# PCBMINI2.net
KiCad netlist of a schematic drawn in EAGLE
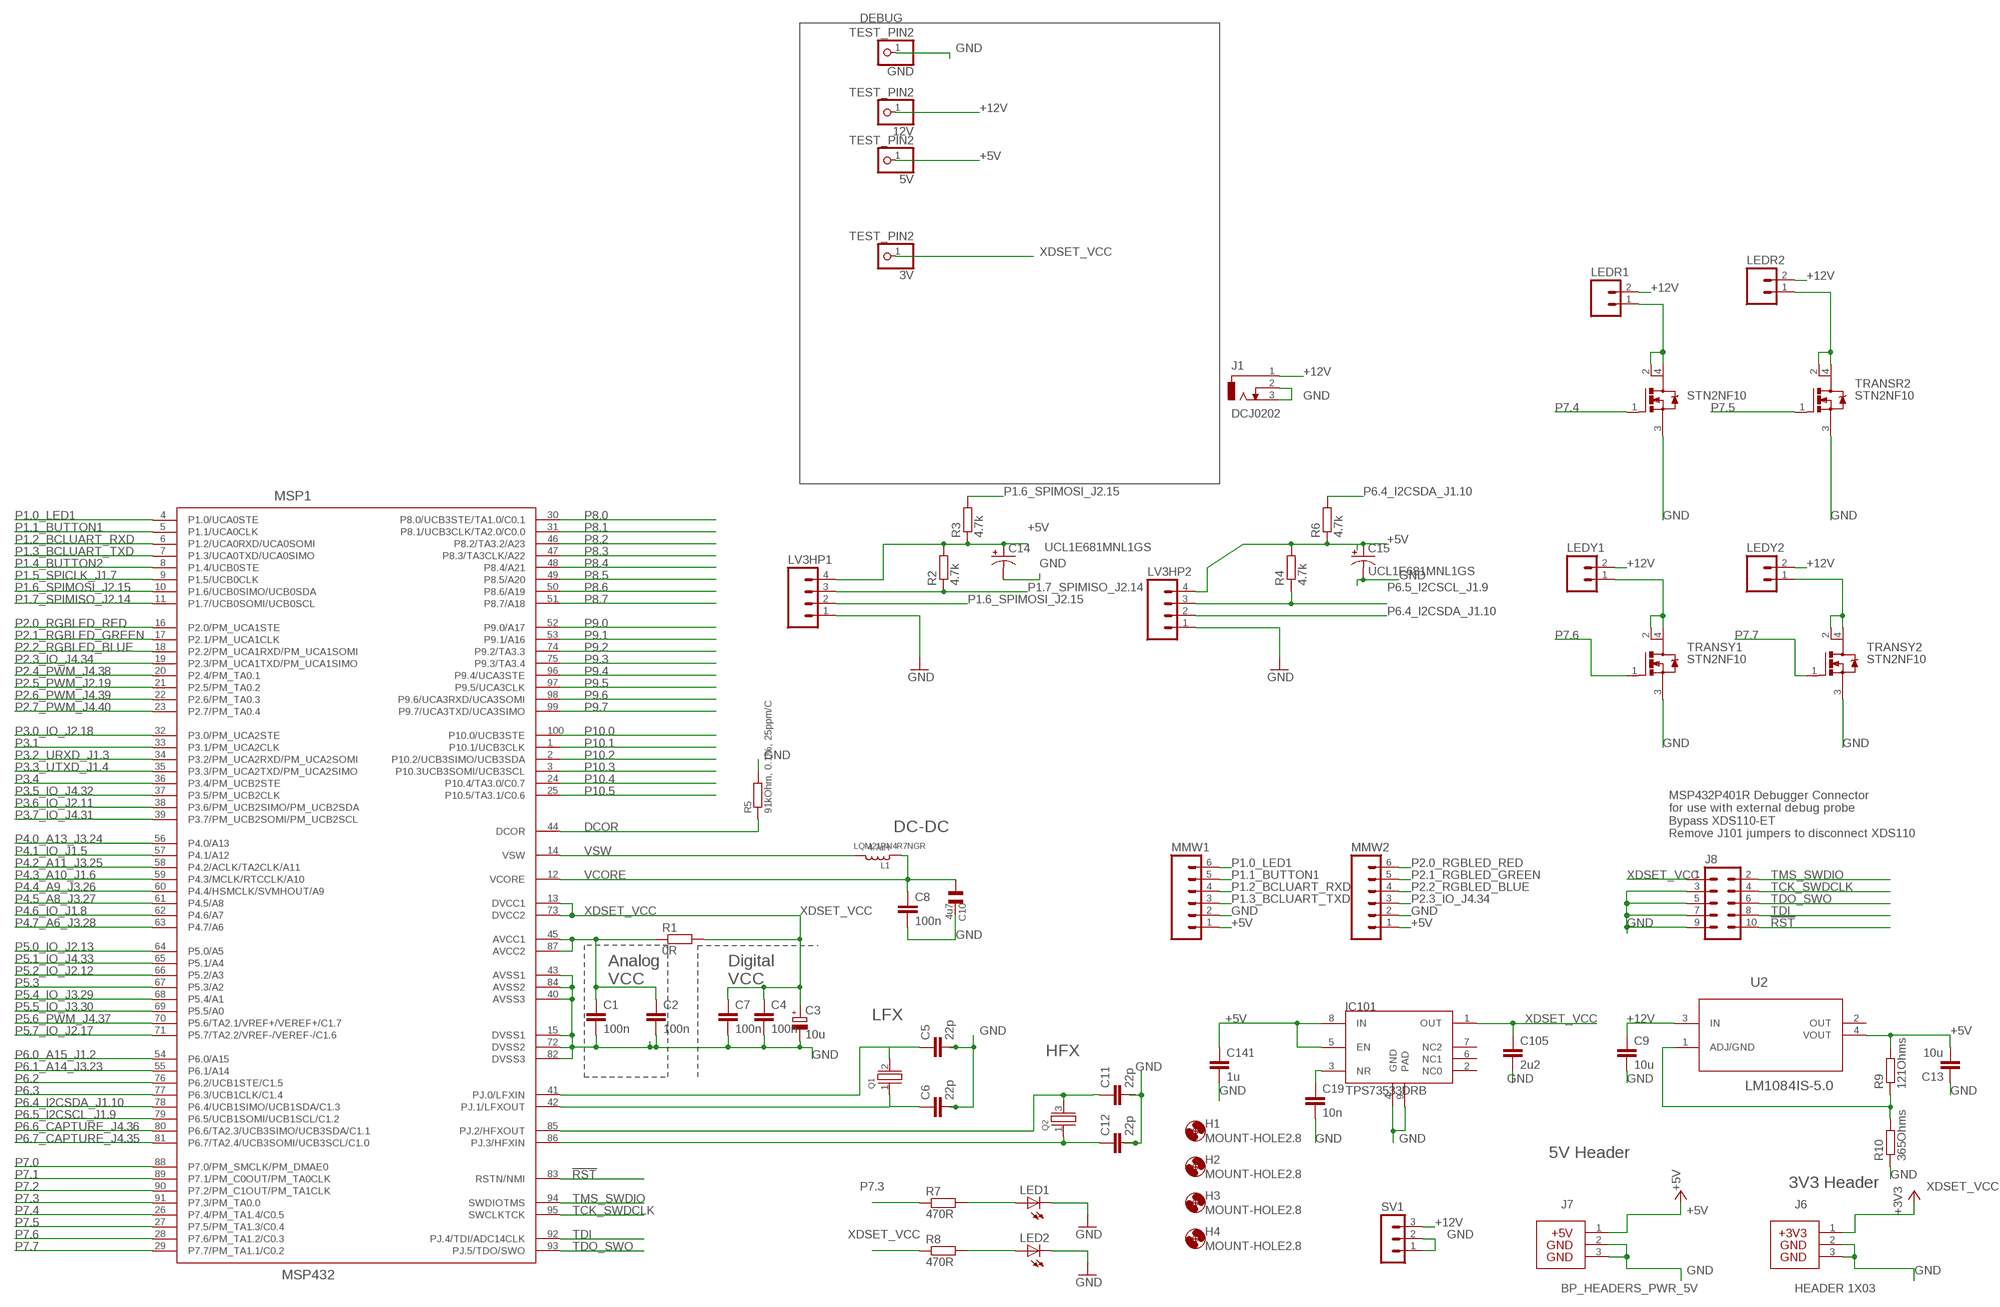
[diagram p0: schematic, sheet 1, part 1 of 2]
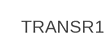
[diagram p1: schematic, sheet 1, part 2 of 2]

(export (version "E")
  (design (tool "Eeschema 10.0.6"))
  (components
    (comp (ref "3V")
      (value "TEST_PIN2")
      (footprint "eagle-import:1X01")
      (libsource (lib "eagle-import") (part "PINHD-1X1"))
    )
    (comp (ref "5V")
      (value "TEST_PIN2")
      (footprint "eagle-import:1X01")
      (libsource (lib "eagle-import") (part "PINHD-1X1"))
    )
    (comp (ref "12V")
      (value "TEST_PIN2")
      (footprint "eagle-import:1X01")
      (libsource (lib "eagle-import") (part "PINHD-1X1"))
    )
    (comp (ref "C1")
      (value "100n")
      (footprint "eagle-import:C0805")
      (libsource (lib "eagle-import") (part "C"))
    )
    (comp (ref "C2")
      (value "100n")
      (footprint "eagle-import:C0805")
      (libsource (lib "eagle-import") (part "C"))
    )
    (comp (ref "C3")
      (value "10u")
      (footprint "eagle-import:A_3216-18R")
      (libsource (lib "eagle-import") (part "CPOL-EUA/3216-18R"))
    )
    (comp (ref "C4")
      (value "100n")
      (footprint "eagle-import:C0805")
      (libsource (lib "eagle-import") (part "C"))
    )
    (comp (ref "C5")
      (value "22p")
      (footprint "eagle-import:C0805")
      (libsource (lib "eagle-import") (part "C"))
    )
    (comp (ref "C6")
      (value "22p")
      (footprint "eagle-import:C0805")
      (libsource (lib "eagle-import") (part "C"))
    )
    (comp (ref "C7")
      (value "100n")
      (footprint "eagle-import:C0805")
      (libsource (lib "eagle-import") (part "C"))
    )
    (comp (ref "C8")
      (value "100n")
      (footprint "eagle-import:C0805")
      (libsource (lib "eagle-import") (part "C"))
    )
    (comp (ref "C9")
      (value "10u")
      (footprint "eagle-import:C0805")
      (libsource (lib "eagle-import") (part "C"))
    )
    (comp (ref "C10")
      (value "4u7")
      (footprint "eagle-import:CSMD0805")
      (libsource (lib "eagle-import") (part "CSMD0805"))
    )
    (comp (ref "C11")
      (value "22p")
      (footprint "eagle-import:C0805")
      (libsource (lib "eagle-import") (part "C"))
    )
    (comp (ref "C12")
      (value "22p")
      (footprint "eagle-import:C0805")
      (libsource (lib "eagle-import") (part "C"))
    )
    (comp (ref "C13")
      (value "10u")
      (footprint "eagle-import:C0805")
      (libsource (lib "eagle-import") (part "C"))
    )
    (comp (ref "C14")
      (value "UCL1E681MNL1GS")
      (footprint "eagle-import:CAPAE1030X1350N")
      (fields (field (name "MF") "Nichicon"))
      (libsource (lib "eagle-import") (part "UCL1E681MNL1GS"))
    )
    (comp (ref "C15")
      (value "UCL1E681MNL1GS")
      (footprint "eagle-import:CAPAE1030X1350N")
      (fields (field (name "MF") "Nichicon"))
      (libsource (lib "eagle-import") (part "UCL1E681MNL1GS"))
    )
    (comp (ref "C19")
      (value "10n")
      (footprint "eagle-import:C0603")
      (libsource (lib "eagle-import") (part "C-EUC0603"))
    )
    (comp (ref "C105")
      (value "2u2")
      (footprint "eagle-import:C0603")
      (libsource (lib "eagle-import") (part "C-EUC0603"))
    )
    (comp (ref "C141")
      (value "1u")
      (footprint "eagle-import:C0603")
      (libsource (lib "eagle-import") (part "C-EUC0603"))
    )
    (comp (ref "GND")
      (value "TEST_PIN2")
      (footprint "eagle-import:1X01")
      (libsource (lib "eagle-import") (part "PINHD-1X1"))
    )
    (comp (ref "H1")
      (value "MOUNT-HOLE2.8")
      (footprint "eagle-import:2,8")
      (libsource (lib "eagle-import") (part "MOUNT-HOLE2.8"))
    )
    (comp (ref "H2")
      (value "MOUNT-HOLE2.8")
      (footprint "eagle-import:2,8")
      (libsource (lib "eagle-import") (part "MOUNT-HOLE2.8"))
    )
    (comp (ref "H3")
      (value "MOUNT-HOLE2.8")
      (footprint "eagle-import:2,8")
      (libsource (lib "eagle-import") (part "MOUNT-HOLE2.8"))
    )
    (comp (ref "H4")
      (value "MOUNT-HOLE2.8")
      (footprint "eagle-import:2,8")
      (libsource (lib "eagle-import") (part "MOUNT-HOLE2.8"))
    )
    (comp (ref "IC101")
      (value "TPS73533DRB")
      (footprint "eagle-import:SON8")
      (libsource (lib "eagle-import") (part "TPS73633DRB"))
    )
    (comp (ref "J1")
      (value "DCJ0202")
      (footprint "eagle-import:DCJ0202")
      (libsource (lib "eagle-import") (part "DCJ0202"))
    )
    (comp (ref "J6")
      (value "HEADER 1X03")
      (footprint "eagle-import:3PIN_PWR_3V3")
      (libsource (lib "eagle-import") (part "BP_HEADERS_PWR_3V3-TH100"))
    )
    (comp (ref "J7")
      (value "BP_HEADERS_PWR_5V")
      (footprint "eagle-import:3PIN_PWR_5V")
      (libsource (lib "eagle-import") (part "BP_HEADERS_PWR_5V"))
    )
    (comp (ref "J8")
      (value "DEBUG_ARM-10")
      (footprint "eagle-import:ARM-10")
      (libsource (lib "eagle-import") (part "DEBUG_ARM-10"))
    )
    (comp (ref "L1")
      (value "4.7uH")
      (footprint "eagle-import:0806")
      (libsource (lib "eagle-import") (part "LQM2MP_G0"))
    )
    (comp (ref "LED1")
      (value "LED_E")
      (footprint "eagle-import:LED_1206")
      (libsource (lib "eagle-import") (part "LED_E"))
    )
    (comp (ref "LED2")
      (value "LED_E")
      (footprint "eagle-import:LED_1206")
      (libsource (lib "eagle-import") (part "LED_E"))
    )
    (comp (ref "LEDR1")
      (value "MA02")
      (footprint "eagle-import:02PA")
      (libsource (lib "eagle-import") (part "MA02"))
    )
    (comp (ref "LEDR2")
      (value "MA02")
      (footprint "eagle-import:02PA")
      (libsource (lib "eagle-import") (part "MA02"))
    )
    (comp (ref "LEDY1")
      (value "MA02")
      (footprint "eagle-import:02PA")
      (libsource (lib "eagle-import") (part "MA02"))
    )
    (comp (ref "LEDY2")
      (value "MA02")
      (footprint "eagle-import:02PA")
      (libsource (lib "eagle-import") (part "MA02"))
    )
    (comp (ref "LV3HP1")
      (value "MA04")
      (footprint "eagle-import:04PA")
      (libsource (lib "eagle-import") (part "MA04"))
    )
    (comp (ref "LV3HP2")
      (value "MA04")
      (footprint "eagle-import:04PA")
      (libsource (lib "eagle-import") (part "MA04"))
    )
    (comp (ref "MMW1")
      (value "MA06")
      (footprint "eagle-import:06PA")
      (libsource (lib "eagle-import") (part "MA06"))
    )
    (comp (ref "MMW2")
      (value "MA06")
      (footprint "eagle-import:06PA")
      (libsource (lib "eagle-import") (part "MA06"))
    )
    (comp (ref "MSP1")
      (value "MSP432")
      (footprint "eagle-import:PZ100")
      (libsource (lib "eagle-import") (part "MSP432"))
    )
    (comp (ref "Q1")
      (value "CRYSTALLF_GENERAL")
      (footprint "eagle-import:LF_XTAL")
      (libsource (lib "eagle-import") (part "CRYSTALLF_GENERAL"))
    )
    (comp (ref "Q2")
      (value "CRYSTALEPSON_FA-238")
      (footprint "eagle-import:FA-238")
      (libsource (lib "eagle-import") (part "CRYSTALEPSON_FA-238"))
    )
    (comp (ref "R1")
      (value "0R")
      (footprint "eagle-import:R0805")
      (libsource (lib "eagle-import") (part "R"))
    )
    (comp (ref "R2")
      (value "4.7k")
      (footprint "eagle-import:R0805")
      (libsource (lib "eagle-import") (part "R"))
    )
    (comp (ref "R3")
      (value "4.7k")
      (footprint "eagle-import:R0805")
      (libsource (lib "eagle-import") (part "R"))
    )
    (comp (ref "R4")
      (value "4.7k")
      (footprint "eagle-import:R0805")
      (libsource (lib "eagle-import") (part "R"))
    )
    (comp (ref "R5")
      (value "91kOhm, 0.1%, 25ppm/C")
      (footprint "eagle-import:0805")
      (libsource (lib "eagle-import") (part "R_0805"))
    )
    (comp (ref "R6")
      (value "4.7k")
      (footprint "eagle-import:R0805")
      (libsource (lib "eagle-import") (part "R"))
    )
    (comp (ref "R7")
      (value "470R")
      (footprint "eagle-import:R0805")
      (libsource (lib "eagle-import") (part "R"))
    )
    (comp (ref "R8")
      (value "470R")
      (footprint "eagle-import:R0805")
      (libsource (lib "eagle-import") (part "R"))
    )
    (comp (ref "R9")
      (value "121Ohms")
      (footprint "eagle-import:R0805")
      (libsource (lib "eagle-import") (part "R"))
    )
    (comp (ref "R10")
      (value "365Ohms")
      (footprint "eagle-import:R0805")
      (libsource (lib "eagle-import") (part "R"))
    )
    (comp (ref "SV1")
      (value "MA03-1")
      (footprint "eagle-import:MA03-1")
      (libsource (lib "eagle-import") (part "MA03-1"))
    )
    (comp (ref "TRANSR1")
      (value "STN2NF10")
      (footprint "eagle-import:SOT230P700X180-4N")
      (fields (field (name "MF") "STMicroelectronics"))
      (libsource (lib "eagle-import") (part "STN2NF10"))
    )
    (comp (ref "TRANSR2")
      (value "STN2NF10")
      (footprint "eagle-import:SOT230P700X180-4N")
      (fields (field (name "MF") "STMicroelectronics"))
      (libsource (lib "eagle-import") (part "STN2NF10"))
    )
    (comp (ref "TRANSY1")
      (value "STN2NF10")
      (footprint "eagle-import:SOT230P700X180-4N")
      (fields (field (name "MF") "STMicroelectronics"))
      (libsource (lib "eagle-import") (part "STN2NF10"))
    )
    (comp (ref "TRANSY2")
      (value "STN2NF10")
      (footprint "eagle-import:SOT230P700X180-4N")
      (fields (field (name "MF") "STMicroelectronics"))
      (libsource (lib "eagle-import") (part "STN2NF10"))
    )
    (comp (ref "U2")
      (value "LM1084IS-5.0")
      (footprint "eagle-import:TO254P1435X457-3N")
      (fields (field (name "MF") "Rohm"))
      (libsource (lib "eagle-import") (part "LM1084IS-5.0"))
    )
  )
  (nets
    (net (code "1") (name "+3V3") (class "Default")
      (node (ref "3V") (pin "1") (pinfunction "1_1") (pintype "passive"))
      (node (ref "C105") (pin "1") (pinfunction "1_1") (pintype "passive"))
      (node (ref "C3") (pin "+") (pinfunction "+_+") (pintype "passive"))
      (node (ref "C4") (pin "1") (pinfunction "1_1") (pintype "passive"))
      (node (ref "C7") (pin "1") (pinfunction "1_1") (pintype "passive"))
      (node (ref "IC101") (pin "1") (pinfunction "OUT_1") (pintype "bidirectional"))
      (node (ref "J6") (pin "1") (pinfunction "1_1") (pintype "bidirectional"))
      (node (ref "J8") (pin "1") (pinfunction "1_1") (pintype "passive"))
      (node (ref "MSP1") (pin "13") (pinfunction "DVCC1_13") (pintype "power_in"))
      (node (ref "MSP1") (pin "73") (pinfunction "DVCC2_73") (pintype "power_in"))
      (node (ref "R1") (pin "2") (pinfunction "2_2") (pintype "passive"))
      (node (ref "R8") (pin "1") (pinfunction "1_1") (pintype "passive"))
    )
    (net (code "2") (name "+5V") (class "Default")
      (node (ref "5V") (pin "1") (pinfunction "1_1") (pintype "passive"))
      (node (ref "C13") (pin "2") (pinfunction "2_2") (pintype "passive"))
      (node (ref "C14") (pin "A") (pinfunction "+_A") (pintype "passive"))
      (node (ref "C141") (pin "1") (pinfunction "1_1") (pintype "passive"))
      (node (ref "C15") (pin "A") (pinfunction "+_A") (pintype "passive"))
      (node (ref "IC101") (pin "5") (pinfunction "EN_5") (pintype "bidirectional"))
      (node (ref "IC101") (pin "8") (pinfunction "IN_8") (pintype "bidirectional"))
      (node (ref "J7") (pin "1") (pinfunction "1_1") (pintype "bidirectional"))
      (node (ref "LV3HP1") (pin "4") (pinfunction "4_4") (pintype "passive"))
      (node (ref "LV3HP2") (pin "4") (pinfunction "4_4") (pintype "passive"))
      (node (ref "MMW1") (pin "1") (pinfunction "1_1") (pintype "passive"))
      (node (ref "MMW2") (pin "1") (pinfunction "1_1") (pintype "passive"))
      (node (ref "R2") (pin "2") (pinfunction "2_2") (pintype "passive"))
      (node (ref "R3") (pin "1") (pinfunction "1_1") (pintype "passive"))
      (node (ref "R4") (pin "2") (pinfunction "2_2") (pintype "passive"))
      (node (ref "R6") (pin "1") (pinfunction "1_1") (pintype "passive"))
      (node (ref "R9") (pin "2") (pinfunction "2_2") (pintype "passive"))
      (node (ref "U2") (pin "4") (pinfunction "VOUT_4") (pintype "output"))
    )
    (net (code "3") (name "/+12V") (class "Default")
      (node (ref "12V") (pin "1") (pinfunction "1_1") (pintype "passive"))
      (node (ref "C9") (pin "1") (pinfunction "1_1") (pintype "passive"))
      (node (ref "J1") (pin "1") (pinfunction "1_1") (pintype "passive"))
      (node (ref "LEDR1") (pin "2") (pinfunction "2_2") (pintype "passive"))
      (node (ref "LEDR2") (pin "2") (pinfunction "2_2") (pintype "passive"))
      (node (ref "LEDY1") (pin "2") (pinfunction "2_2") (pintype "passive"))
      (node (ref "LEDY2") (pin "2") (pinfunction "2_2") (pintype "passive"))
      (node (ref "SV1") (pin "3") (pinfunction "3_3") (pintype "passive"))
      (node (ref "U2") (pin "3") (pinfunction "IN_3") (pintype "power_in"))
    )
    (net (code "4") (name "/DCOR") (class "Default")
      (node (ref "MSP1") (pin "44") (pinfunction "DCOR_44") (pintype "power_in"))
      (node (ref "R5") (pin "1") (pinfunction "1_1") (pintype "passive"))
    )
    (net (code "5") (name "/P1.0_LED1") (class "Default")
      (node (ref "MMW1") (pin "6") (pinfunction "6_6") (pintype "passive"))
      (node (ref "MSP1") (pin "4") (pinfunction "P1.0/UCA0STE_4") (pintype "power_in"))
    )
    (net (code "6") (name "/P1.1_BUTTON1") (class "Default")
      (node (ref "MMW1") (pin "5") (pinfunction "5_5") (pintype "passive"))
      (node (ref "MSP1") (pin "5") (pinfunction "P1.1/UCA0CLK_5") (pintype "power_in"))
    )
    (net (code "7") (name "/P1.2_BCLUART_RXD") (class "Default")
      (node (ref "MMW1") (pin "4") (pinfunction "4_4") (pintype "passive"))
      (node (ref "MSP1") (pin "6") (pinfunction "P1.2/UCA0RXD/UCA0SOMI_6") (pintype "power_in"))
    )
    (net (code "8") (name "/P1.3_BCLUART_TXD") (class "Default")
      (node (ref "MMW1") (pin "3") (pinfunction "3_3") (pintype "passive"))
      (node (ref "MSP1") (pin "7") (pinfunction "P1.3/UCA0TXD/UCA0SIMO_7") (pintype "power_in"))
    )
    (net (code "9") (name "/P1.4_BUTTON2") (class "Default")
      (node (ref "MSP1") (pin "8") (pinfunction "P1.4/UCB0STE_8") (pintype "power_in"))
    )
    (net (code "10") (name "/P1.5_SPICLK_J1.7") (class "Default")
      (node (ref "MSP1") (pin "9") (pinfunction "P1.5/UCB0CLK_9") (pintype "power_in"))
    )
    (net (code "11") (name "/P1.6_SPIMOSI_J2.15") (class "Default")
      (node (ref "LV3HP1") (pin "2") (pinfunction "2_2") (pintype "passive"))
      (node (ref "MSP1") (pin "10") (pinfunction "P1.6/UCB0SIMO/UCB0SDA_10") (pintype "power_in"))
      (node (ref "R3") (pin "2") (pinfunction "2_2") (pintype "passive"))
    )
    (net (code "12") (name "/P1.7_SPIMISO_J2.14") (class "Default")
      (node (ref "LV3HP1") (pin "3") (pinfunction "3_3") (pintype "passive"))
      (node (ref "MSP1") (pin "11") (pinfunction "P1.7/UCB0SOMI/UCB0SCL_11") (pintype "power_in"))
      (node (ref "R2") (pin "1") (pinfunction "1_1") (pintype "passive"))
    )
    (net (code "13") (name "/P2.0_RGBLED_RED") (class "Default")
      (node (ref "MMW2") (pin "6") (pinfunction "6_6") (pintype "passive"))
      (node (ref "MSP1") (pin "16") (pinfunction "P2.0/PM_UCA1STE_16") (pintype "power_in"))
    )
    (net (code "14") (name "/P2.1_RGBLED_GREEN") (class "Default")
      (node (ref "MMW2") (pin "5") (pinfunction "5_5") (pintype "passive"))
      (node (ref "MSP1") (pin "17") (pinfunction "P2.1/PM_UCA1CLK_17") (pintype "power_in"))
    )
    (net (code "15") (name "/P2.2_RGBLED_BLUE") (class "Default")
      (node (ref "MMW2") (pin "4") (pinfunction "4_4") (pintype "passive"))
      (node (ref "MSP1") (pin "18") (pinfunction "P2.2/PM_UCA1RXD/PM_UCA1SOMI_18") (pintype "power_in"))
    )
    (net (code "16") (name "/P2.3_IO_J4.34") (class "Default")
      (node (ref "MMW2") (pin "3") (pinfunction "3_3") (pintype "passive"))
      (node (ref "MSP1") (pin "19") (pinfunction "P2.3/PM_UCA1TXD/PM_UCA1SIMO_19") (pintype "power_in"))
    )
    (net (code "17") (name "/P2.4_PWM_J4.38") (class "Default")
      (node (ref "MSP1") (pin "20") (pinfunction "P2.4/PM_TA0.1_20") (pintype "power_in"))
    )
    (net (code "18") (name "/P2.5_PWM_J2.19") (class "Default")
      (node (ref "MSP1") (pin "21") (pinfunction "P2.5/PM_TA0.2_21") (pintype "power_in"))
    )
    (net (code "19") (name "/P2.6_PWM_J4.39") (class "Default")
      (node (ref "MSP1") (pin "22") (pinfunction "P2.6/PM_TA0.3_22") (pintype "power_in"))
    )
    (net (code "20") (name "/P2.7_PWM_J4.40") (class "Default")
      (node (ref "MSP1") (pin "23") (pinfunction "P2.7/PM_TA0.4_23") (pintype "power_in"))
    )
    (net (code "21") (name "/P3.0_IO_J2.18") (class "Default")
      (node (ref "MSP1") (pin "32") (pinfunction "P3.0/PM_UCA2STE_32") (pintype "power_in"))
    )
    (net (code "22") (name "/P3.1") (class "Default")
      (node (ref "MSP1") (pin "33") (pinfunction "P3.1/PM_UCA2CLK_33") (pintype "power_in"))
    )
    (net (code "23") (name "/P3.2_URXD_J1.3") (class "Default")
      (node (ref "MSP1") (pin "34") (pinfunction "P3.2/PM_UCA2RXD/PM_UCA2SOMI_34") (pintype "power_in"))
    )
    (net (code "24") (name "/P3.3_UTXD_J1.4") (class "Default")
      (node (ref "MSP1") (pin "35") (pinfunction "P3.3/PM_UCA2TXD/PM_UCA2SIMO_35") (pintype "power_in"))
    )
    (net (code "25") (name "/P3.4") (class "Default")
      (node (ref "MSP1") (pin "36") (pinfunction "P3.4/PM_UCB2STE_36") (pintype "power_in"))
    )
    (net (code "26") (name "/P3.5_IO_J4.32") (class "Default")
      (node (ref "MSP1") (pin "37") (pinfunction "P3.5/PM_UCB2CLK_37") (pintype "power_in"))
    )
    (net (code "27") (name "/P3.6_IO_J2.11") (class "Default")
      (node (ref "MSP1") (pin "38") (pinfunction "P3.6/PM_UCB2SIMO/PM_UCB2SDA_38") (pintype "power_in"))
    )
    (net (code "28") (name "/P3.7_IO_J4.31") (class "Default")
      (node (ref "MSP1") (pin "39") (pinfunction "P3.7/PM_UCB2SOMI/PM_UCB2SCL_39") (pintype "power_in"))
    )
    (net (code "29") (name "/P4.0_A13_J3.24") (class "Default")
      (node (ref "MSP1") (pin "56") (pinfunction "P4.0/A13_56") (pintype "power_in"))
    )
    (net (code "30") (name "/P4.1_IO_J1.5") (class "Default")
      (node (ref "MSP1") (pin "57") (pinfunction "P4.1/A12_57") (pintype "power_in"))
    )
    (net (code "31") (name "/P4.2_A11_J3.25") (class "Default")
      (node (ref "MSP1") (pin "58") (pinfunction "P4.2/ACLK/TA2CLK/A11_58") (pintype "power_in"))
    )
    (net (code "32") (name "/P4.3_A10_J1.6") (class "Default")
      (node (ref "MSP1") (pin "59") (pinfunction "P4.3/MCLK/RTCCLK/A10_59") (pintype "power_in"))
    )
    (net (code "33") (name "/P4.4_A9_J3.26") (class "Default")
      (node (ref "MSP1") (pin "60") (pinfunction "P4.4/HSMCLK/SVMHOUT/A9_60") (pintype "power_in"))
    )
    (net (code "34") (name "/P4.5_A8_J3.27") (class "Default")
      (node (ref "MSP1") (pin "61") (pinfunction "P4.5/A8_61") (pintype "power_in"))
    )
    (net (code "35") (name "/P4.6_IO_J1.8") (class "Default")
      (node (ref "MSP1") (pin "62") (pinfunction "P4.6/A7_62") (pintype "power_in"))
    )
    (net (code "36") (name "/P4.7_A6_J3.28") (class "Default")
      (node (ref "MSP1") (pin "63") (pinfunction "P4.7/A6_63") (pintype "power_in"))
    )
    (net (code "37") (name "/P5.0_IO_J2.13") (class "Default")
      (node (ref "MSP1") (pin "64") (pinfunction "P5.0/A5_64") (pintype "power_in"))
    )
    (net (code "38") (name "/P5.1_IO_J4.33") (class "Default")
      (node (ref "MSP1") (pin "65") (pinfunction "P5.1/A4_65") (pintype "power_in"))
    )
    (net (code "39") (name "/P5.2_IO_J2.12") (class "Default")
      (node (ref "MSP1") (pin "66") (pinfunction "P5.2/A3_66") (pintype "power_in"))
    )
    (net (code "40") (name "/P5.3") (class "Default")
      (node (ref "MSP1") (pin "67") (pinfunction "P5.3/A2_67") (pintype "power_in"))
    )
    (net (code "41") (name "/P5.4_IO_J3.29") (class "Default")
      (node (ref "MSP1") (pin "68") (pinfunction "P5.4/A1_68") (pintype "power_in"))
    )
    (net (code "42") (name "/P5.5_IO_J3.30") (class "Default")
      (node (ref "MSP1") (pin "69") (pinfunction "P5.5/A0_69") (pintype "power_in"))
    )
    (net (code "43") (name "/P5.6_PWM_J4.37") (class "Default")
      (node (ref "MSP1") (pin "70") (pinfunction "P5.6/TA2.1/VREF+/VEREF+/C1.7_70") (pintype "power_in"))
    )
    (net (code "44") (name "/P5.7_IO_J2.17") (class "Default")
      (node (ref "MSP1") (pin "71") (pinfunction "P5.7/TA2.2/VREF-/VEREF-/C1.6_71") (pintype "power_in"))
    )
    (net (code "45") (name "/P6.0_A15_J1.2") (class "Default")
      (node (ref "MSP1") (pin "54") (pinfunction "P6.0/A15_54") (pintype "power_in"))
    )
    (net (code "46") (name "/P6.1_A14_J3.23") (class "Default")
      (node (ref "MSP1") (pin "55") (pinfunction "P6.1/A14_55") (pintype "power_in"))
    )
    (net (code "47") (name "/P6.2") (class "Default")
      (node (ref "MSP1") (pin "76") (pinfunction "P6.2/UCB1STE/C1.5_76") (pintype "power_in"))
    )
    (net (code "48") (name "/P6.3") (class "Default")
      (node (ref "MSP1") (pin "77") (pinfunction "P6.3/UCB1CLK/C1.4_77") (pintype "power_in"))
    )
    (net (code "49") (name "/P6.4_I2CSDA_J1.10") (class "Default")
      (node (ref "LV3HP2") (pin "2") (pinfunction "2_2") (pintype "passive"))
      (node (ref "MSP1") (pin "78") (pinfunction "P6.4/UCB1SIMO/UCB1SDA/C1.3_78") (pintype "power_in"))
      (node (ref "R6") (pin "2") (pinfunction "2_2") (pintype "passive"))
    )
    (net (code "50") (name "/P6.5_I2CSCL_J1.9") (class "Default")
      (node (ref "LV3HP2") (pin "3") (pinfunction "3_3") (pintype "passive"))
      (node (ref "MSP1") (pin "79") (pinfunction "P6.5/UCB1SOMI/UCB1SCL/C1.2_79") (pintype "power_in"))
      (node (ref "R4") (pin "1") (pinfunction "1_1") (pintype "passive"))
    )
    (net (code "51") (name "/P6.6_CAPTURE_J4.36") (class "Default")
      (node (ref "MSP1") (pin "80") (pinfunction "P6.6/TA2.3/UCB3SIMO/UCB3SDA/C1.1_80") (pintype "power_in"))
    )
    (net (code "52") (name "/P6.7_CAPTURE_J4.35") (class "Default")
      (node (ref "MSP1") (pin "81") (pinfunction "P6.7/TA2.4/UCB3SOMI/UCB3SCL/C1.0_81") (pintype "power_in"))
    )
    (net (code "53") (name "/P7.0") (class "Default")
      (node (ref "MSP1") (pin "88") (pinfunction "P7.0/PM_SMCLK/PM_DMAE0_88") (pintype "power_in"))
    )
    (net (code "54") (name "/P7.1") (class "Default")
      (node (ref "MSP1") (pin "89") (pinfunction "P7.1/PM_C0OUT/PM_TA0CLK_89") (pintype "power_in"))
    )
    (net (code "55") (name "/P7.2") (class "Default")
      (node (ref "MSP1") (pin "90") (pinfunction "P7.2/PM_C1OUT/PM_TA1CLK_90") (pintype "power_in"))
    )
    (net (code "56") (name "/P7.3") (class "Default")
      (node (ref "MSP1") (pin "91") (pinfunction "P7.3/PM_TA0.0_91") (pintype "power_in"))
      (node (ref "R7") (pin "1") (pinfunction "1_1") (pintype "passive"))
    )
    (net (code "57") (name "/P7.4") (class "Default")
      (node (ref "MSP1") (pin "26") (pinfunction "P7.4/PM_TA1.4/C0.5_26") (pintype "power_in"))
      (node (ref "TRANSR1") (pin "1") (pinfunction "G_1") (pintype "passive"))
    )
    (net (code "58") (name "/P7.5") (class "Default")
      (node (ref "MSP1") (pin "27") (pinfunction "P7.5/PM_TA1.3/C0.4_27") (pintype "power_in"))
      (node (ref "TRANSR2") (pin "1") (pinfunction "G_1") (pintype "passive"))
    )
    (net (code "59") (name "/P7.6") (class "Default")
      (node (ref "MSP1") (pin "28") (pinfunction "P7.6/PM_TA1.2/C0.3_28") (pintype "power_in"))
      (node (ref "TRANSY1") (pin "1") (pinfunction "G_1") (pintype "passive"))
    )
    (net (code "60") (name "/P7.7") (class "Default")
      (node (ref "MSP1") (pin "29") (pinfunction "P7.7/PM_TA1.1/C0.2_29") (pintype "power_in"))
      (node (ref "TRANSY2") (pin "1") (pinfunction "G_1") (pintype "passive"))
    )
    (net (code "61") (name "/P8.0") (class "Default")
      (node (ref "MSP1") (pin "30") (pinfunction "P8.0/UCB3STE/TA1.0/C0.1_30") (pintype "power_in"))
    )
    (net (code "62") (name "/P8.1") (class "Default")
      (node (ref "MSP1") (pin "31") (pinfunction "P8.1/UCB3CLK/TA2.0/C0.0_31") (pintype "power_in"))
    )
    (net (code "63") (name "/P8.2") (class "Default")
      (node (ref "MSP1") (pin "46") (pinfunction "P8.2/TA3.2/A23_46") (pintype "power_in"))
    )
    (net (code "64") (name "/P8.3") (class "Default")
      (node (ref "MSP1") (pin "47") (pinfunction "P8.3/TA3CLK/A22_47") (pintype "power_in"))
    )
    (net (code "65") (name "/P8.4") (class "Default")
      (node (ref "MSP1") (pin "48") (pinfunction "P8.4/A21_48") (pintype "power_in"))
    )
    (net (code "66") (name "/P8.5") (class "Default")
      (node (ref "MSP1") (pin "49") (pinfunction "P8.5/A20_49") (pintype "power_in"))
    )
    (net (code "67") (name "/P8.6") (class "Default")
      (node (ref "MSP1") (pin "50") (pinfunction "P8.6/A19_50") (pintype "power_in"))
    )
    (net (code "68") (name "/P8.7") (class "Default")
      (node (ref "MSP1") (pin "51") (pinfunction "P8.7/A18_51") (pintype "power_in"))
    )
    (net (code "69") (name "/P9.0") (class "Default")
      (node (ref "MSP1") (pin "52") (pinfunction "P9.0/A17_52") (pintype "power_in"))
    )
    (net (code "70") (name "/P9.1") (class "Default")
      (node (ref "MSP1") (pin "53") (pinfunction "P9.1/A16_53") (pintype "power_in"))
    )
    (net (code "71") (name "/P9.2") (class "Default")
      (node (ref "MSP1") (pin "74") (pinfunction "P9.2/TA3.3_74") (pintype "power_in"))
    )
    (net (code "72") (name "/P9.3") (class "Default")
      (node (ref "MSP1") (pin "75") (pinfunction "P9.3/TA3.4_75") (pintype "power_in"))
    )
    (net (code "73") (name "/P9.4") (class "Default")
      (node (ref "MSP1") (pin "96") (pinfunction "P9.4/UCA3STE_96") (pintype "power_in"))
    )
    (net (code "74") (name "/P9.5") (class "Default")
      (node (ref "MSP1") (pin "97") (pinfunction "P9.5/UCA3CLK_97") (pintype "power_in"))
    )
    (net (code "75") (name "/P9.6") (class "Default")
      (node (ref "MSP1") (pin "98") (pinfunction "P9.6/UCA3RXD/UCA3SOMI_98") (pintype "power_in"))
    )
    (net (code "76") (name "/P9.7") (class "Default")
      (node (ref "MSP1") (pin "99") (pinfunction "P9.7/UCA3TXD/UCA3SIMO_99") (pintype "power_in"))
    )
    (net (code "77") (name "/P10.0") (class "Default")
      (node (ref "MSP1") (pin "100") (pinfunction "P10.0/UCB3STE_100") (pintype "power_in"))
    )
    (net (code "78") (name "/P10.1") (class "Default")
      (node (ref "MSP1") (pin "1") (pinfunction "P10.1/UCB3CLK_1") (pintype "power_in"))
    )
    (net (code "79") (name "/P10.2") (class "Default")
      (node (ref "MSP1") (pin "2") (pinfunction "P10.2/UCB3SIMO/UCB3SDA_2") (pintype "power_in"))
    )
    (net (code "80") (name "/P10.3") (class "Default")
      (node (ref "MSP1") (pin "3") (pinfunction "P10.3UCB3SOMI/UCB3SCL_3") (pintype "power_in"))
    )
    (net (code "81") (name "/P10.4") (class "Default")
      (node (ref "MSP1") (pin "24") (pinfunction "P10.4/TA3.0/C0.7_24") (pintype "power_in"))
    )
    (net (code "82") (name "/P10.5") (class "Default")
      (node (ref "MSP1") (pin "25") (pinfunction "P10.5/TA3.1/C0.6_25") (pintype "power_in"))
    )
    (net (code "83") (name "/TCK_SWDCLK") (class "Default")
      (node (ref "J8") (pin "4") (pinfunction "4_4") (pintype "passive"))
      (node (ref "MSP1") (pin "95") (pinfunction "SWCLKTCK_95") (pintype "power_in"))
    )
    (net (code "84") (name "/TDI") (class "Default")
      (node (ref "J8") (pin "8") (pinfunction "8_8") (pintype "passive"))
      (node (ref "MSP1") (pin "92") (pinfunction "PJ.4/TDI/ADC14CLK_92") (pintype "power_in"))
    )
    (net (code "85") (name "/TDO_SWO") (class "Default")
      (node (ref "J8") (pin "6") (pinfunction "6_6") (pintype "passive"))
      (node (ref "MSP1") (pin "93") (pinfunction "PJ.5/TDO/SWO_93") (pintype "power_in"))
    )
    (net (code "86") (name "/TMS_SWDIO") (class "Default")
      (node (ref "J8") (pin "2") (pinfunction "2_2") (pintype "passive"))
      (node (ref "MSP1") (pin "94") (pinfunction "SWDIOTMS_94") (pintype "power_in"))
    )
    (net (code "87") (name "/VCORE") (class "Default")
      (node (ref "C10") (pin "1") (pinfunction "1_1") (pintype "passive"))
      (node (ref "C8") (pin "1") (pinfunction "1_1") (pintype "passive"))
      (node (ref "L1") (pin "1") (pinfunction "1_1") (pintype "passive"))
      (node (ref "MSP1") (pin "12") (pinfunction "VCORE_12") (pintype "power_in"))
    )
    (net (code "88") (name "/VSW") (class "Default")
      (node (ref "L1") (pin "2") (pinfunction "2_2") (pintype "passive"))
      (node (ref "MSP1") (pin "14") (pinfunction "VSW_14") (pintype "power_in"))
    )
    (net (code "89") (name "/~{RST}") (class "Default")
      (node (ref "J8") (pin "10") (pinfunction "10_10") (pintype "passive"))
      (node (ref "MSP1") (pin "83") (pinfunction "RSTN/NMI_83") (pintype "power_in"))
    )
    (net (code "90") (name "GND") (class "Default")
      (node (ref "C1") (pin "2") (pinfunction "2_2") (pintype "passive"))
      (node (ref "C10") (pin "2") (pinfunction "2_2") (pintype "passive"))
      (node (ref "C105") (pin "2") (pinfunction "2_2") (pintype "passive"))
      (node (ref "C11") (pin "2") (pinfunction "2_2") (pintype "passive"))
      (node (ref "C12") (pin "2") (pinfunction "2_2") (pintype "passive"))
      (node (ref "C13") (pin "1") (pinfunction "1_1") (pintype "passive"))
      (node (ref "C14") (pin "C") (pinfunction "-_C") (pintype "passive"))
      (node (ref "C141") (pin "2") (pinfunction "2_2") (pintype "passive"))
      (node (ref "C15") (pin "C") (pinfunction "-_C") (pintype "passive"))
      (node (ref "C19") (pin "2") (pinfunction "2_2") (pintype "passive"))
      (node (ref "C2") (pin "2") (pinfunction "2_2") (pintype "passive"))
      (node (ref "C3") (pin "-") (pinfunction "-_-") (pintype "passive"))
      (node (ref "C4") (pin "2") (pinfunction "2_2") (pintype "passive"))
      (node (ref "C5") (pin "2") (pinfunction "2_2") (pintype "passive"))
      (node (ref "C6") (pin "2") (pinfunction "2_2") (pintype "passive"))
      (node (ref "C7") (pin "2") (pinfunction "2_2") (pintype "passive"))
      (node (ref "C8") (pin "2") (pinfunction "2_2") (pintype "passive"))
      (node (ref "C9") (pin "2") (pinfunction "2_2") (pintype "passive"))
      (node (ref "GND") (pin "1") (pinfunction "1_1") (pintype "passive"))
      (node (ref "IC101") (pin "4") (pinfunction "GND_4") (pintype "bidirectional"))
      (node (ref "IC101") (pin "9") (pinfunction "PAD_9") (pintype "bidirectional"))
      (node (ref "J1") (pin "2") (pinfunction "2_2") (pintype "passive"))
      (node (ref "J1") (pin "3") (pinfunction "3_3") (pintype "passive"))
      (node (ref "J6") (pin "2") (pinfunction "2_2") (pintype "bidirectional"))
      (node (ref "J6") (pin "3") (pinfunction "3_3") (pintype "bidirectional"))
      (node (ref "J7") (pin "2") (pinfunction "2_2") (pintype "bidirectional"))
      (node (ref "J7") (pin "3") (pinfunction "3_3") (pintype "bidirectional"))
      (node (ref "J8") (pin "3") (pinfunction "3_3") (pintype "passive"))
      (node (ref "J8") (pin "5") (pinfunction "5_5") (pintype "passive"))
      (node (ref "J8") (pin "7") (pinfunction "7_7") (pintype "passive"))
      (node (ref "J8") (pin "9") (pinfunction "9_9") (pintype "passive"))
      (node (ref "LED1") (pin "C") (pinfunction "C_C") (pintype "passive"))
      (node (ref "LED2") (pin "C") (pinfunction "C_C") (pintype "passive"))
      (node (ref "LV3HP1") (pin "1") (pinfunction "1_1") (pintype "passive"))
      (node (ref "LV3HP2") (pin "1") (pinfunction "1_1") (pintype "passive"))
      (node (ref "MMW1") (pin "2") (pinfunction "2_2") (pintype "passive"))
      (node (ref "MMW2") (pin "2") (pinfunction "2_2") (pintype "passive"))
      (node (ref "MSP1") (pin "15") (pinfunction "DVSS1_15") (pintype "power_in"))
      (node (ref "MSP1") (pin "40") (pinfunction "AVSS3_40") (pintype "power_in"))
      (node (ref "MSP1") (pin "43") (pinfunction "AVSS1_43") (pintype "power_in"))
      (node (ref "MSP1") (pin "72") (pinfunction "DVSS2_72") (pintype "power_in"))
      (node (ref "MSP1") (pin "82") (pinfunction "DVSS3_82") (pintype "power_in"))
      (node (ref "MSP1") (pin "84") (pinfunction "AVSS2_84") (pintype "power_in"))
      (node (ref "R10") (pin "1") (pinfunction "1_1") (pintype "passive"))
      (node (ref "R5") (pin "2") (pinfunction "2_2") (pintype "passive"))
      (node (ref "SV1") (pin "1") (pinfunction "1_1") (pintype "passive"))
      (node (ref "SV1") (pin "2") (pinfunction "2_2") (pintype "passive"))
      (node (ref "TRANSR1") (pin "3") (pinfunction "S_3") (pintype "passive"))
      (node (ref "TRANSR2") (pin "3") (pinfunction "S_3") (pintype "passive"))
      (node (ref "TRANSY1") (pin "3") (pinfunction "S_3") (pintype "passive"))
      (node (ref "TRANSY2") (pin "3") (pinfunction "S_3") (pintype "passive"))
    )
    (net (code "91") (name "Net-(IC101-NR)") (class "Default")
      (node (ref "C19") (pin "1") (pinfunction "1_1") (pintype "passive"))
      (node (ref "IC101") (pin "3") (pinfunction "NR_3") (pintype "bidirectional"))
    )
    (net (code "92") (name "Net-(LED1-PadA)") (class "Default")
      (node (ref "LED1") (pin "A") (pinfunction "A_A") (pintype "passive"))
      (node (ref "R7") (pin "2") (pinfunction "2_2") (pintype "passive"))
    )
    (net (code "93") (name "Net-(LED2-PadA)") (class "Default")
      (node (ref "LED2") (pin "A") (pinfunction "A_A") (pintype "passive"))
      (node (ref "R8") (pin "2") (pinfunction "2_2") (pintype "passive"))
    )
    (net (code "94") (name "Net-(LEDR1-Pad1)") (class "Default")
      (node (ref "LEDR1") (pin "1") (pinfunction "1_1") (pintype "passive"))
      (node (ref "TRANSR1") (pin "2") (pinfunction "D_2") (pintype "passive"))
      (node (ref "TRANSR1") (pin "4") (pinfunction "D_4") (pintype "passive"))
    )
    (net (code "95") (name "Net-(LEDR2-Pad1)") (class "Default")
      (node (ref "LEDR2") (pin "1") (pinfunction "1_1") (pintype "passive"))
      (node (ref "TRANSR2") (pin "2") (pinfunction "D_2") (pintype "passive"))
      (node (ref "TRANSR2") (pin "4") (pinfunction "D_4") (pintype "passive"))
    )
    (net (code "96") (name "Net-(LEDY1-Pad1)") (class "Default")
      (node (ref "LEDY1") (pin "1") (pinfunction "1_1") (pintype "passive"))
      (node (ref "TRANSY1") (pin "2") (pinfunction "D_2") (pintype "passive"))
      (node (ref "TRANSY1") (pin "4") (pinfunction "D_4") (pintype "passive"))
    )
    (net (code "97") (name "Net-(LEDY2-Pad1)") (class "Default")
      (node (ref "LEDY2") (pin "1") (pinfunction "1_1") (pintype "passive"))
      (node (ref "TRANSY2") (pin "2") (pinfunction "D_2") (pintype "passive"))
      (node (ref "TRANSY2") (pin "4") (pinfunction "D_4") (pintype "passive"))
    )
    (net (code "98") (name "Net-(MSP1-AVCC1)") (class "Default")
      (node (ref "C1") (pin "1") (pinfunction "1_1") (pintype "passive"))
      (node (ref "C2") (pin "1") (pinfunction "1_1") (pintype "passive"))
      (node (ref "MSP1") (pin "45") (pinfunction "AVCC1_45") (pintype "power_in"))
      (node (ref "MSP1") (pin "87") (pinfunction "AVCC2_87") (pintype "power_in"))
      (node (ref "R1") (pin "1") (pinfunction "1_1") (pintype "passive"))
    )
    (net (code "99") (name "Net-(MSP1-PJ.0{slash}LFXIN)") (class "Default")
      (node (ref "C5") (pin "1") (pinfunction "1_1") (pintype "passive"))
      (node (ref "MSP1") (pin "41") (pinfunction "PJ.0/LFXIN_41") (pintype "power_in"))
      (node (ref "Q1") (pin "2") (pinfunction "2_2") (pintype "passive"))
    )
    (net (code "100") (name "Net-(MSP1-PJ.1{slash}LFXOUT)") (class "Default")
      (node (ref "C6") (pin "1") (pinfunction "1_1") (pintype "passive"))
      (node (ref "MSP1") (pin "42") (pinfunction "PJ.1/LFXOUT_42") (pintype "power_in"))
      (node (ref "Q1") (pin "1") (pinfunction "1_1") (pintype "passive"))
    )
    (net (code "101") (name "Net-(MSP1-PJ.2{slash}HFXOUT)") (class "Default")
      (node (ref "C11") (pin "1") (pinfunction "1_1") (pintype "passive"))
      (node (ref "MSP1") (pin "85") (pinfunction "PJ.2/HFXOUT_85") (pintype "power_in"))
      (node (ref "Q2") (pin "3") (pinfunction "2_3") (pintype "passive"))
    )
    (net (code "102") (name "Net-(MSP1-PJ.3{slash}HFXIN)") (class "Default")
      (node (ref "C12") (pin "1") (pinfunction "1_1") (pintype "passive"))
      (node (ref "MSP1") (pin "86") (pinfunction "PJ.3/HFXIN_86") (pintype "power_in"))
      (node (ref "Q2") (pin "1") (pinfunction "1_1") (pintype "passive"))
    )
    (net (code "103") (name "Net-(U2-ADJ{slash}GND)") (class "Default")
      (node (ref "R10") (pin "2") (pinfunction "2_2") (pintype "passive"))
      (node (ref "R9") (pin "1") (pinfunction "1_1") (pintype "passive"))
      (node (ref "U2") (pin "1") (pinfunction "ADJ/GND_1") (pintype "passive"))
    )
    (net (code "104") (name "unconnected-(IC101-NC0-Pad2)") (class "Default")
      (node (ref "IC101") (pin "2") (pinfunction "NC0_2") (pintype "bidirectional"))
    )
    (net (code "105") (name "unconnected-(IC101-NC1-Pad6)") (class "Default")
      (node (ref "IC101") (pin "6") (pinfunction "NC1_6") (pintype "bidirectional"))
    )
    (net (code "106") (name "unconnected-(IC101-NC2-Pad7)") (class "Default")
      (node (ref "IC101") (pin "7") (pinfunction "NC2_7") (pintype "bidirectional"))
    )
    (net (code "107") (name "unconnected-(U2-OUT-Pad2)") (class "Default")
      (node (ref "U2") (pin "2") (pinfunction "OUT_2") (pintype "output"))
    )
  )
)
